# Clock_Extension.net
KiCad netlist of a schematic drawn in EAGLE
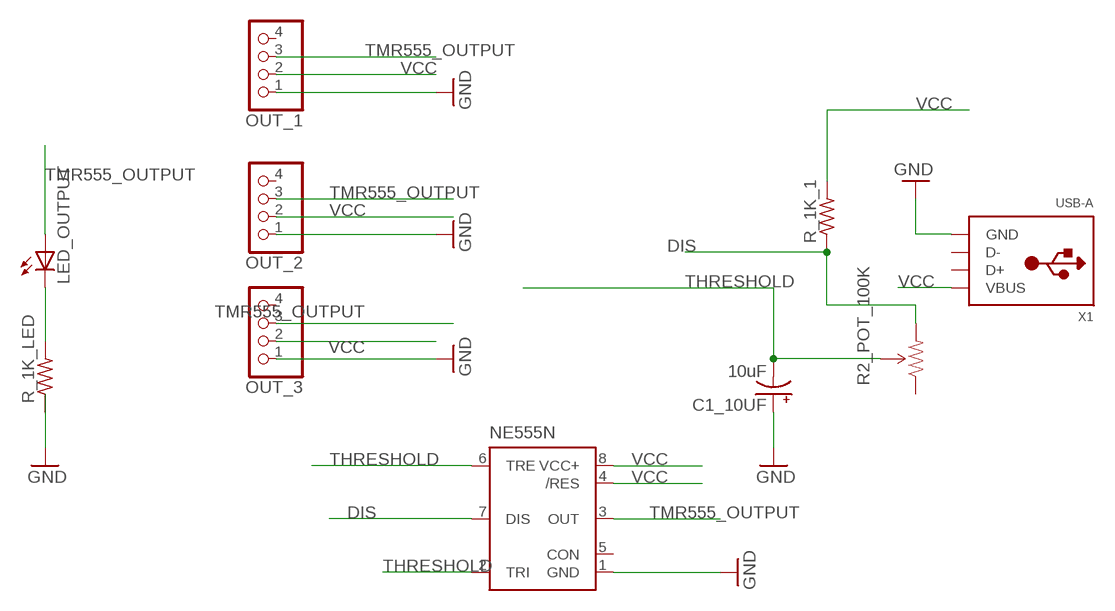
[diagram p0: schematic, sheet 1]

(export (version "E")
  (design (tool "Eeschema 10.0.6"))
  (components
    (comp (ref "C1_10UF")
      (value "10uF")
      (footprint "eagle-import:EIA3216")
      (libsource (lib "eagle-import") (part "10UF-16V-10%(TANT)"))
    )
    (comp (ref "LED_OUTPUT")
      (value "LEDSMT1206")
      (footprint "eagle-import:1206")
      (libsource (lib "eagle-import") (part "LEDSMT1206"))
    )
    (comp (ref "NE555N")
      (value "NE555D")
      (footprint "eagle-import:SO08")
      (libsource (lib "eagle-import") (part "NE555D"))
    )
    (comp (ref "OUT_1")
      (value "PINHD-1X4")
      (footprint "eagle-import:1X04")
      (libsource (lib "eagle-import") (part "PINHD-1X4"))
    )
    (comp (ref "OUT_2")
      (value "PINHD-1X4")
      (footprint "eagle-import:1X04")
      (libsource (lib "eagle-import") (part "PINHD-1X4"))
    )
    (comp (ref "OUT_3")
      (value "PINHD-1X4")
      (footprint "eagle-import:1X04")
      (libsource (lib "eagle-import") (part "PINHD-1X4"))
    )
    (comp (ref "R2_POT_100K")
      (value "TRIMPOTPTH")
      (footprint "eagle-import:TRIM_POT_PTH")
      (libsource (lib "eagle-import") (part "TRIMPOTPTH"))
    )
    (comp (ref "R_1K_1")
      (value "R-US_R1206")
      (footprint "eagle-import:R1206")
      (libsource (lib "eagle-import") (part "R-US_R1206"))
    )
    (comp (ref "R_1K_LED")
      (value "R-US_R1206")
      (footprint "eagle-import:R1206")
      (libsource (lib "eagle-import") (part "R-US_R1206"))
    )
    (comp (ref "X1")
      (value "USB-A")
      (footprint "eagle-import:MOLEX_480371000")
      (libsource (lib "eagle-import") (part "USB-A"))
    )
  )
  (nets
    (net (code "1") (name "/DIS") (class "Default")
      (node (ref "NE555N") (pin "7") (pinfunction "DIS_7") (pintype "input"))
      (node (ref "R2_POT_100K") (pin "3") (pinfunction "CW_3") (pintype "passive"))
      (node (ref "R_1K_1") (pin "1") (pinfunction "1_1") (pintype "passive"))
    )
    (net (code "2") (name "/THRESHOLD") (class "Default")
      (node (ref "C1_10UF") (pin "C") (pinfunction "-_C") (pintype "passive"))
      (node (ref "NE555N") (pin "2") (pinfunction "TRI_2") (pintype "input"))
      (node (ref "NE555N") (pin "6") (pinfunction "TRE_6") (pintype "input"))
      (node (ref "R2_POT_100K") (pin "2") (pinfunction "WIPER_2") (pintype "passive"))
    )
    (net (code "3") (name "/TMR555_OUTPUT") (class "Default")
      (node (ref "LED_OUTPUT") (pin "A") (pinfunction "A_A") (pintype "passive"))
      (node (ref "NE555N") (pin "3") (pinfunction "OUT_3") (pintype "output"))
      (node (ref "OUT_1") (pin "3") (pinfunction "3_3") (pintype "passive"))
      (node (ref "OUT_2") (pin "3") (pinfunction "3_3") (pintype "passive"))
      (node (ref "OUT_3") (pin "3") (pinfunction "3_3") (pintype "passive"))
    )
    (net (code "4") (name "/VCC") (class "Default")
      (node (ref "NE555N") (pin "4") (pinfunction "/RES_4") (pintype "input"))
      (node (ref "NE555N") (pin "8") (pinfunction "VCC+_8") (pintype "power_in"))
      (node (ref "OUT_1") (pin "2") (pinfunction "2_2") (pintype "passive"))
      (node (ref "OUT_2") (pin "2") (pinfunction "2_2") (pintype "passive"))
      (node (ref "OUT_3") (pin "2") (pinfunction "2_2") (pintype "passive"))
      (node (ref "R_1K_1") (pin "2") (pinfunction "2_2") (pintype "passive"))
      (node (ref "X1") (pin "1") (pinfunction "VBUS_1") (pintype "power_in"))
    )
    (net (code "5") (name "GND") (class "Default")
      (node (ref "C1_10UF") (pin "A") (pinfunction "+_A") (pintype "passive"))
      (node (ref "NE555N") (pin "1") (pinfunction "GND_1") (pintype "power_in"))
      (node (ref "OUT_1") (pin "1") (pinfunction "1_1") (pintype "passive"))
      (node (ref "OUT_2") (pin "1") (pinfunction "1_1") (pintype "passive"))
      (node (ref "OUT_3") (pin "1") (pinfunction "1_1") (pintype "passive"))
      (node (ref "R_1K_LED") (pin "1") (pinfunction "1_1") (pintype "passive"))
      (node (ref "X1") (pin "4") (pinfunction "GND_4") (pintype "power_in"))
    )
    (net (code "6") (name "Net-(LED_OUTPUT-PadC)") (class "Default")
      (node (ref "LED_OUTPUT") (pin "C") (pinfunction "C_C") (pintype "passive"))
      (node (ref "R_1K_LED") (pin "2") (pinfunction "2_2") (pintype "passive"))
    )
    (net (code "7") (name "unconnected-(NE555N-CON-Pad5)") (class "Default")
      (node (ref "NE555N") (pin "5") (pinfunction "CON_5") (pintype "input"))
    )
    (net (code "8") (name "unconnected-(OUT_1-Pad4)") (class "Default")
      (node (ref "OUT_1") (pin "4") (pinfunction "4_4") (pintype "passive"))
    )
    (net (code "9") (name "unconnected-(OUT_2-Pad4)") (class "Default")
      (node (ref "OUT_2") (pin "4") (pinfunction "4_4") (pintype "passive"))
    )
    (net (code "10") (name "unconnected-(OUT_3-Pad4)") (class "Default")
      (node (ref "OUT_3") (pin "4") (pinfunction "4_4") (pintype "passive"))
    )
    (net (code "11") (name "unconnected-(R2_POT_100K-CCW-Pad1)") (class "Default")
      (node (ref "R2_POT_100K") (pin "1") (pinfunction "CCW_1") (pintype "passive"))
    )
    (net (code "12") (name "unconnected-(X1-D+-Pad3)") (class "Default")
      (node (ref "X1") (pin "3") (pinfunction "D+_3") (pintype "bidirectional"))
    )
    (net (code "13") (name "unconnected-(X1-D--Pad2)") (class "Default")
      (node (ref "X1") (pin "2") (pinfunction "D-_2") (pintype "bidirectional"))
    )
  )
)
